# Power.net
KiCad netlist of a schematic drawn in Altium Designer
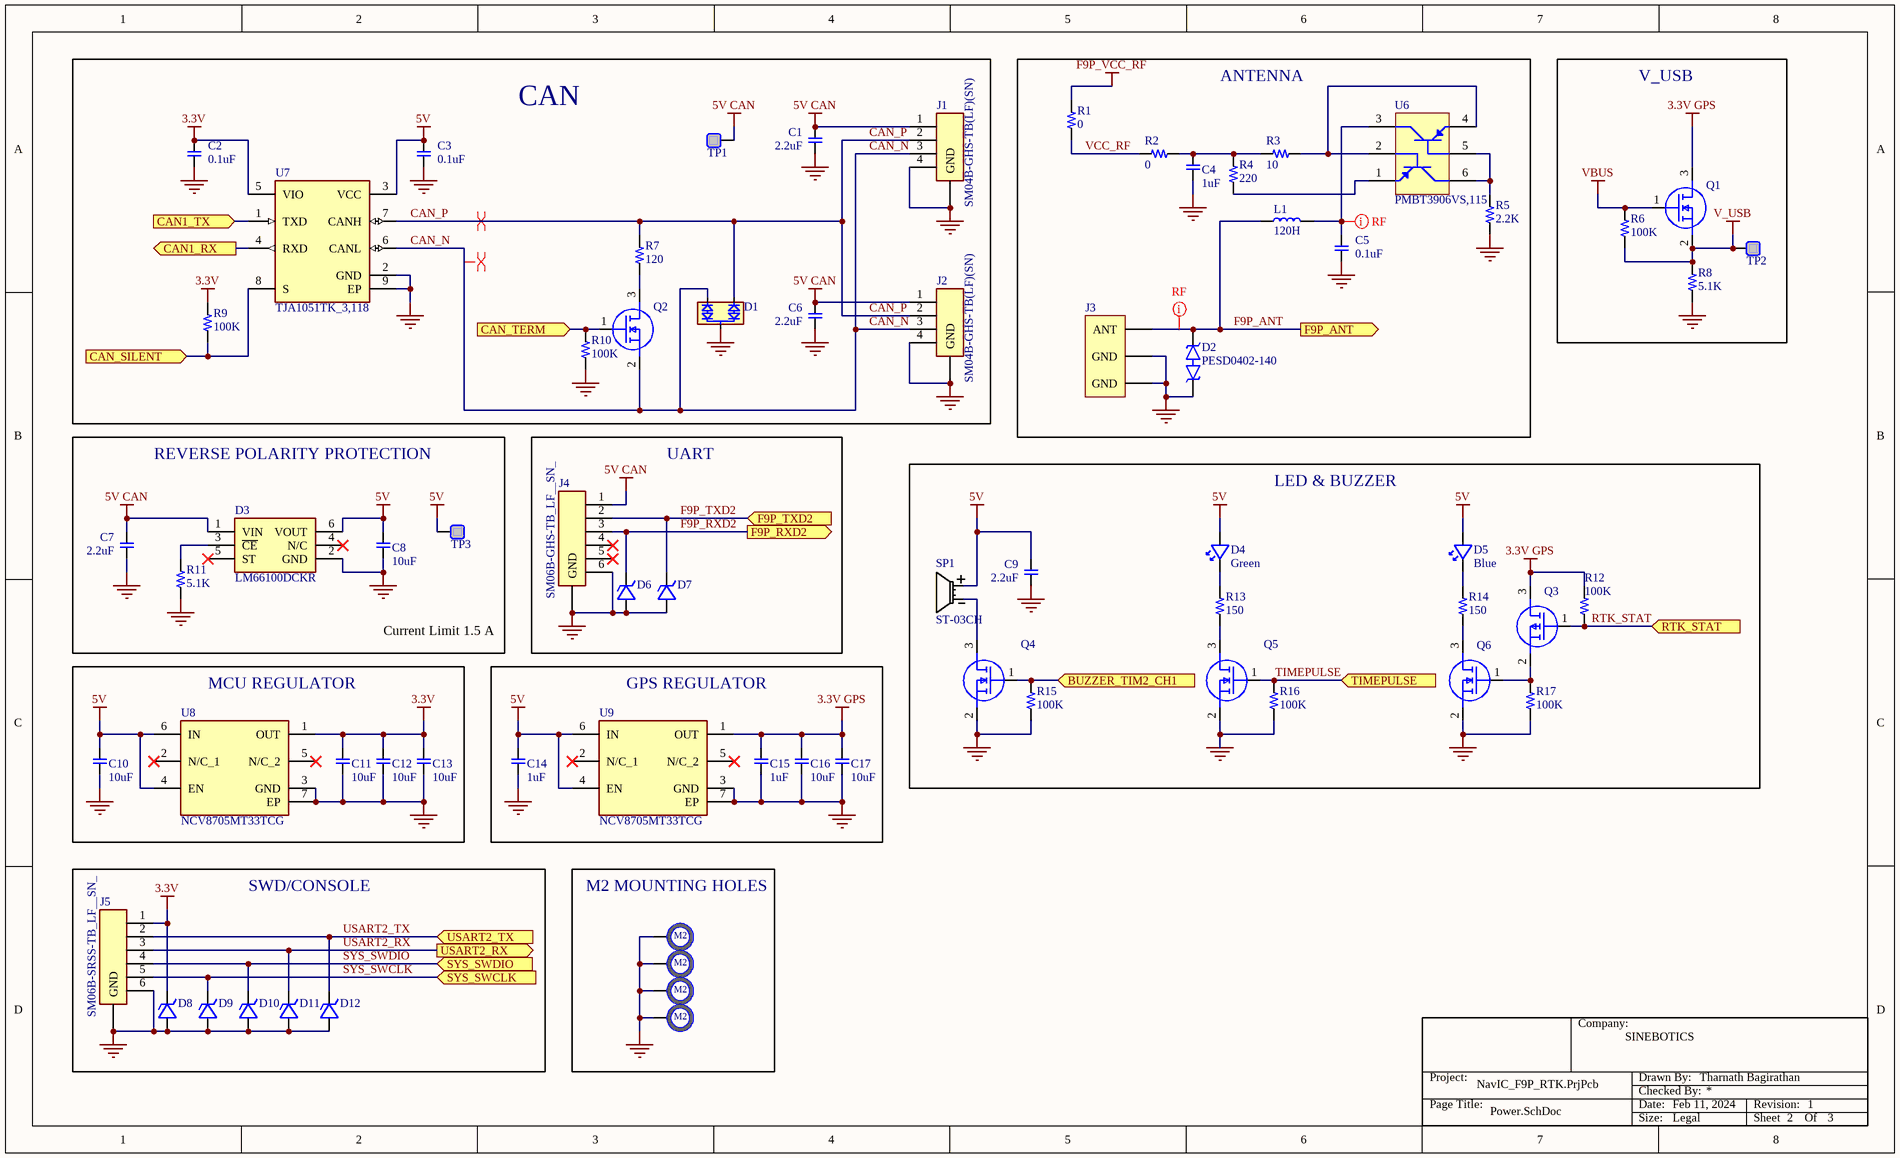
[diagram p0: Power.SchDoc]

(export (version "E")
  (design (tool "Eeschema 10.0.6"))
  (components
    (comp (ref "C1")
      (value "2.2uF")
      (footprint "C0402")
      (description "Capacitor 0402 Generic")
      (fields
        (field (name "MANUFACTURER PART NUMBER") "GRM155R61A225ME95D")
        (field (name "MANUFACTURER") "Murata")
      )
      (libsource (lib "Library") (part "CAP_0402"))
    )
    (comp (ref "C2")
      (value "0.1uF")
      (footprint "C0402")
      (description "Capacitor 0402 Generic")
      (fields
        (field (name "MANUFACTURER PART NUMBER") "0402X104K250CT")
        (field (name "MANUFACTURER") "Walsin Technology Corporation")
      )
      (libsource (lib "Library") (part "CAP_0402"))
    )
    (comp (ref "C3")
      (value "0.1uF")
      (footprint "C0402")
      (description "Capacitor 0402 Generic")
      (fields
        (field (name "MANUFACTURER PART NUMBER") "0402X104K250CT")
        (field (name "MANUFACTURER") "Walsin Technology Corporation")
      )
      (libsource (lib "Library") (part "CAP_0402"))
    )
    (comp (ref "C4")
      (value "1uF")
      (footprint "C0402")
      (description "Capacitor 0402 Generic")
      (fields
        (field (name "MANUFACTURER PART NUMBER") "CL05A105KP5NNNC")
        (field (name "MANUFACTURER") "Samsung Electro-Mechanics")
      )
      (libsource (lib "Library") (part "CAP_0402"))
    )
    (comp (ref "C5")
      (value "0.1uF")
      (footprint "C0402")
      (description "Capacitor 0402 Generic")
      (fields
        (field (name "MANUFACTURER PART NUMBER") "0402X104K250CT")
        (field (name "MANUFACTURER") "Walsin Technology Corporation")
      )
      (libsource (lib "Library") (part "CAP_0402"))
    )
    (comp (ref "C6")
      (value "2.2uF")
      (footprint "C0402")
      (description "Capacitor 0402 Generic")
      (fields
        (field (name "MANUFACTURER PART NUMBER") "GRM155R61A225ME95D")
        (field (name "MANUFACTURER") "Murata")
      )
      (libsource (lib "Library") (part "CAP_0402"))
    )
    (comp (ref "C7")
      (value "2.2uF")
      (footprint "C0402")
      (description "Capacitor 0402 Generic")
      (fields
        (field (name "MANUFACTURER PART NUMBER") "GRM155R61A225ME95D")
        (field (name "MANUFACTURER") "Murata")
      )
      (libsource (lib "Library") (part "CAP_0402"))
    )
    (comp (ref "C8")
      (value "10uF")
      (footprint "C0402")
      (description "Capacitor 0402 Generic")
      (fields
        (field (name "MANUFACTURER PART NUMBER") "CL05A106MP8NUB8")
        (field (name "MANUFACTURER") "Samsung Electro-Mechanics")
      )
      (libsource (lib "Library") (part "CAP_0402"))
    )
    (comp (ref "C9")
      (value "2.2uF")
      (footprint "C0402")
      (description "Capacitor 0402 Generic")
      (fields
        (field (name "MANUFACTURER PART NUMBER") "GRM155R61A225ME95D")
        (field (name "MANUFACTURER") "Murata")
      )
      (libsource (lib "Library") (part "CAP_0402"))
    )
    (comp (ref "C10")
      (value "10uF")
      (footprint "C0402")
      (description "Capacitor 0402 Generic")
      (fields
        (field (name "MANUFACTURER PART NUMBER") "CL05A106MP8NUB8")
        (field (name "MANUFACTURER") "Samsung Electro-Mechanics")
      )
      (libsource (lib "Library") (part "CAP_0402"))
    )
    (comp (ref "C11")
      (value "10uF")
      (footprint "C0402")
      (description "Capacitor 0402 Generic")
      (fields
        (field (name "MANUFACTURER PART NUMBER") "CL05A106MP8NUB8")
        (field (name "MANUFACTURER") "Samsung Electro-Mechanics")
      )
      (libsource (lib "Library") (part "CAP_0402"))
    )
    (comp (ref "C12")
      (value "10uF")
      (footprint "C0402")
      (description "Capacitor 0402 Generic")
      (fields
        (field (name "MANUFACTURER PART NUMBER") "CL05A106MP8NUB8")
        (field (name "MANUFACTURER") "Samsung Electro-Mechanics")
      )
      (libsource (lib "Library") (part "CAP_0402"))
    )
    (comp (ref "C13")
      (value "10uF")
      (footprint "C0402")
      (description "Capacitor 0402 Generic")
      (fields
        (field (name "MANUFACTURER PART NUMBER") "CL05A106MP8NUB8")
        (field (name "MANUFACTURER") "Samsung Electro-Mechanics")
      )
      (libsource (lib "Library") (part "CAP_0402"))
    )
    (comp (ref "C14")
      (value "1uF")
      (footprint "C0402")
      (description "Capacitor 0402 Generic")
      (fields
        (field (name "MANUFACTURER PART NUMBER") "CL05A105KP5NNNC")
        (field (name "MANUFACTURER") "Samsung Electro-Mechanics")
      )
      (libsource (lib "Library") (part "CAP_0402"))
    )
    (comp (ref "C15")
      (value "1uF")
      (footprint "C0402")
      (description "Capacitor 0402 Generic")
      (fields
        (field (name "MANUFACTURER PART NUMBER") "CL05A105KP5NNNC")
        (field (name "MANUFACTURER") "Samsung Electro-Mechanics")
      )
      (libsource (lib "Library") (part "CAP_0402"))
    )
    (comp (ref "C16")
      (value "10uF")
      (footprint "C0402")
      (description "Capacitor 0402 Generic")
      (fields
        (field (name "MANUFACTURER PART NUMBER") "CL05A106MP8NUB8")
        (field (name "MANUFACTURER") "Samsung Electro-Mechanics")
      )
      (libsource (lib "Library") (part "CAP_0402"))
    )
    (comp (ref "C17")
      (value "10uF")
      (footprint "C0402")
      (description "Capacitor 0402 Generic")
      (fields
        (field (name "MANUFACTURER PART NUMBER") "CL05A106MP8NUB8")
        (field (name "MANUFACTURER") "Samsung Electro-Mechanics")
      )
      (libsource (lib "Library") (part "CAP_0402"))
    )
    (comp (ref "D1")
      (value "PESD1CAN-UX")
      (footprint "SamacSys:PESD1CANUX")
      (description "Diode")
      (libsource (lib "SamacSys") (part "PESD1CAN-UX"))
    )
    (comp (ref "D2")
      (value "PESD0402-140")
      (footprint "SamacSys:DIONC1005X43N")
      (description "TVS Diode (Bi-directional)")
      (libsource (lib "SamacSys") (part "PESD0402-140"))
    )
    (comp (ref "D3")
      (value "LM66100DCKR")
      (footprint "SamacSys:SOP65P210X110-6N")
      (description "Diode")
      (libsource (lib "SamacSys") (part "LM66100DCKR"))
    )
    (comp (ref "D4")
      (value "Green")
      (footprint "SamacSys:LTSTS110TBKT")
      (description "LED")
      (fields
        (field (name "ARROW PART NUMBER") "LTST-S110TBKT")
        (field (name "MANUFACTURER PART NUMBER") "LTST-S110KGKT")
      )
      (libsource (lib "Schlib") (part "LTST-S110KGKT"))
    )
    (comp (ref "D5")
      (value "Blue")
      (footprint "SamacSys:LTSTS110TBKT")
      (description "LED")
      (fields (field (name "ARROW PART NUMBER") "LTST-S110TBKT"))
      (libsource (lib "SamacSys") (part "LTST-S110TBKT"))
    )
    (comp (ref "D6")
      (value "ESD9C3.3ST5G")
      (footprint "SamacSys:SODFL1006X40N")
      (description "TVS Diode (Uni-directional)")
      (fields (field (name "ARROW PART NUMBER") "SZESD9C3.3ST5G"))
      (libsource (lib "SamacSys") (part "ESD9C3.3ST5G"))
    )
    (comp (ref "D7")
      (value "ESD9C3.3ST5G")
      (footprint "SamacSys:SODFL1006X40N")
      (description "TVS Diode (Uni-directional)")
      (fields (field (name "ARROW PART NUMBER") "SZESD9C3.3ST5G"))
      (libsource (lib "SamacSys") (part "ESD9C3.3ST5G"))
    )
    (comp (ref "D8")
      (value "ESD9C3.3ST5G")
      (footprint "SamacSys:SODFL1006X40N")
      (description "TVS Diode (Uni-directional)")
      (fields (field (name "ARROW PART NUMBER") "SZESD9C3.3ST5G"))
      (libsource (lib "SamacSys") (part "ESD9C3.3ST5G"))
    )
    (comp (ref "D9")
      (value "ESD9C3.3ST5G")
      (footprint "SamacSys:SODFL1006X40N")
      (description "TVS Diode (Uni-directional)")
      (fields (field (name "ARROW PART NUMBER") "SZESD9C3.3ST5G"))
      (libsource (lib "SamacSys") (part "ESD9C3.3ST5G"))
    )
    (comp (ref "D10")
      (value "ESD9C3.3ST5G")
      (footprint "SamacSys:SODFL1006X40N")
      (description "TVS Diode (Uni-directional)")
      (fields (field (name "ARROW PART NUMBER") "SZESD9C3.3ST5G"))
      (libsource (lib "SamacSys") (part "ESD9C3.3ST5G"))
    )
    (comp (ref "D11")
      (value "ESD9C3.3ST5G")
      (footprint "SamacSys:SODFL1006X40N")
      (description "TVS Diode (Uni-directional)")
      (fields (field (name "ARROW PART NUMBER") "SZESD9C3.3ST5G"))
      (libsource (lib "SamacSys") (part "ESD9C3.3ST5G"))
    )
    (comp (ref "D12")
      (value "ESD9C3.3ST5G")
      (footprint "SamacSys:SODFL1006X40N")
      (description "TVS Diode (Uni-directional)")
      (fields (field (name "ARROW PART NUMBER") "SZESD9C3.3ST5G"))
      (libsource (lib "SamacSys") (part "ESD9C3.3ST5G"))
    )
    (comp (ref "H1") (value "M2") (footprint "Hole_M2") (libsource (lib "Schlib") (part "Hole_M2")))
    (comp (ref "H2") (value "M2") (footprint "Hole_M2") (libsource (lib "Schlib") (part "Hole_M2")))
    (comp (ref "H3") (value "M2") (footprint "Hole_M2") (libsource (lib "Schlib") (part "Hole_M2")))
    (comp (ref "H4") (value "M2") (footprint "Hole_M2") (libsource (lib "Schlib") (part "Hole_M2")))
    (comp (ref "J1")
      (value "SM04B-GHS-TB(LF)(SN)")
      (footprint "SamacSys:SM04B-GHS-TB")
      (description "Connector")
      (libsource (lib "SamacSys") (part "SM04B-GHS-TB(LF)(SN)"))
    )
    (comp (ref "J2")
      (value "SM04B-GHS-TB(LF)(SN)")
      (footprint "SamacSys:SM04B-GHS-TB")
      (description "Connector")
      (libsource (lib "SamacSys") (part "SM04B-GHS-TB(LF)(SN)"))
    )
    (comp (ref "J3")
      (value "0734150963")
      (footprint "PcbLib:MOLEX_0734150963")
      (description "MMCX Connector Jack, Female Socket 50Ohm Board Edge, Cutout; Surface Mount Solder")
      (fields (field (name "MF") "Molex"))
      (libsource (lib "Schlib") (part "0734150963"))
    )
    (comp (ref "J4")
      (value "SM06B-GHS-TB_LF__SN_")
      (footprint "SamacSys:SM06B-GHS-TB")
      (description "Connector")
      (fields (field (name "MANUFACTURER_PART_NUMBER") "SM06B-GHS-TB(LF)(SN)"))
      (libsource (lib "SamacSys") (part "SM06B-GHS-TB_LF__SN_"))
    )
    (comp (ref "J5")
      (value "SM06B-SRSS-TB_LF__SN_")
      (footprint "SamacSys:SM06BSRSSTBLFSN")
      (description "Connector")
      (fields (field (name "MOUSER PART NUMBER") "SM06B-SRSS-TB(LF)(SN)"))
      (libsource (lib "SamacSys") (part "SM06B-SRSS-TB_LF__SN_"))
    )
    (comp (ref "L1")
      (value "120H")
      (footprint "SamacSys:LQW15CNR20J00B")
      (description "Inductor")
      (fields (field (name "ARROW PART NUMBER") "LQW15ANR12J00D"))
      (libsource (lib "SamacSys") (part "LQW15ANR12J00D"))
    )
    (comp (ref "Q1")
      (value "DMN53D0L-7")
      (footprint "SamacSys:SOT96P240X110-3N")
      (description "MOSFET (N-Channel)")
      (libsource (lib "SamacSys") (part "DMN53D0L-7"))
    )
    (comp (ref "Q2")
      (value "DMN53D0L-7")
      (footprint "SamacSys:SOT96P240X110-3N")
      (description "MOSFET (N-Channel)")
      (libsource (lib "SamacSys") (part "DMN53D0L-7"))
    )
    (comp (ref "Q3")
      (value "BSS223PWH6327XTSA1")
      (footprint "SamacSys:SOT65P210X100-3N")
      (description "MOSFET (P-Channel)")
      (libsource (lib "SamacSys") (part "BSS223PWH6327XTSA1"))
    )
    (comp (ref "Q4")
      (value "DMN53D0L-7")
      (footprint "SamacSys:SOT96P240X110-3N")
      (description "MOSFET (N-Channel)")
      (libsource (lib "SamacSys") (part "DMN53D0L-7"))
    )
    (comp (ref "Q5")
      (value "DMN53D0L-7")
      (footprint "SamacSys:SOT96P240X110-3N")
      (description "MOSFET (N-Channel)")
      (libsource (lib "SamacSys") (part "DMN53D0L-7"))
    )
    (comp (ref "Q6")
      (value "DMN53D0L-7")
      (footprint "SamacSys:SOT96P240X110-3N")
      (description "MOSFET (N-Channel)")
      (libsource (lib "SamacSys") (part "DMN53D0L-7"))
    )
    (comp (ref "R1")
      (value "0")
      (footprint "R0402")
      (description "Resistor 0402 Generic")
      (fields
        (field (name "MANUFACTURER") "Yageo")
        (field (name "MANUFACTURER PART NUMBER") "AC0402JR-070RL")
      )
      (libsource (lib "Library") (part "RES_0402"))
    )
    (comp (ref "R2")
      (value "0")
      (footprint "R0402")
      (description "Resistor 0402 Generic")
      (fields
        (field (name "MANUFACTURER") "Yageo")
        (field (name "MANUFACTURER PART NUMBER") "AC0402JR-070RL")
      )
      (libsource (lib "Library") (part "RES_0402"))
    )
    (comp (ref "R3")
      (value "10")
      (footprint "SamacSys:RESC3225X70N")
      (description "Resistor")
      (fields (field (name "MANUFACTURER_PART_NUMBER") "RMCF1210JT10R0"))
      (libsource (lib "SamacSys") (part "RES_10_1/2W"))
    )
    (comp (ref "R4")
      (value "220")
      (footprint "R0402")
      (description "Resistor 0402 Generic")
      (fields
        (field (name "MANUFACTURER") "Stackpole Electronics Inc")
        (field (name "MANUFACTURER PART NUMBER") "RMCF0402JT220R")
      )
      (libsource (lib "Library") (part "RES_0402"))
    )
    (comp (ref "R5")
      (value "2.2K")
      (footprint "R0402")
      (description "Resistor 0402 Generic")
      (fields
        (field (name "MANUFACTURER") "Yageo")
        (field (name "MANUFACTURER PART NUMBER") "AC0402FR-072K2L")
      )
      (libsource (lib "Library") (part "RES_0402"))
    )
    (comp (ref "R6")
      (value "100K")
      (footprint "R0402")
      (description "Resistor 0402 Generic")
      (fields
        (field (name "MANUFACTURER") "Yageo")
        (field (name "MANUFACTURER PART NUMBER") "AC0402JR-07100KL")
      )
      (libsource (lib "Library") (part "RES_0402"))
    )
    (comp (ref "R7")
      (value "120")
      (footprint "SamacSys:RESC1608X55N")
      (description "Resistor")
      (fields (field (name "MANUFACTURER_PART_NUMBER") "RMCF0603FT120R"))
      (libsource (lib "SamacSys") (part "RES_120"))
    )
    (comp (ref "R8")
      (value "5.1K")
      (footprint "R0402")
      (description "Resistor 0402 Generic")
      (fields
        (field (name "MANUFACTURER") "Yageo")
        (field (name "MANUFACTURER PART NUMBER") "RC0402FR-075K1L")
      )
      (libsource (lib "Library") (part "RES_0402"))
    )
    (comp (ref "R9")
      (value "100K")
      (footprint "R0402")
      (description "Resistor 0402 Generic")
      (fields
        (field (name "MANUFACTURER") "Yageo")
        (field (name "MANUFACTURER PART NUMBER") "AC0402JR-07100KL")
      )
      (libsource (lib "Library") (part "RES_0402"))
    )
    (comp (ref "R10")
      (value "100K")
      (footprint "R0402")
      (description "Resistor 0402 Generic")
      (fields
        (field (name "MANUFACTURER") "Yageo")
        (field (name "MANUFACTURER PART NUMBER") "AC0402JR-07100KL")
      )
      (libsource (lib "Library") (part "RES_0402"))
    )
    (comp (ref "R11")
      (value "5.1K")
      (footprint "R0402")
      (description "Resistor 0402 Generic")
      (fields
        (field (name "MANUFACTURER") "Yageo")
        (field (name "MANUFACTURER PART NUMBER") "RC0402FR-075K1L")
      )
      (libsource (lib "Library") (part "RES_0402"))
    )
    (comp (ref "R12")
      (value "100K")
      (footprint "R0402")
      (description "Resistor 0402 Generic")
      (fields
        (field (name "MANUFACTURER") "Yageo")
        (field (name "MANUFACTURER PART NUMBER") "AC0402JR-07100KL")
      )
      (libsource (lib "Library") (part "RES_0402"))
    )
    (comp (ref "R13")
      (value "150")
      (footprint "R0402")
      (description "Resistor 0402 Generic")
      (fields
        (field (name "MANUFACTURER") "Stackpole Electronics Inc")
        (field (name "MANUFACTURER PART NUMBER") "RC0402FR-07150RL")
      )
      (libsource (lib "Library") (part "RES_0402"))
    )
    (comp (ref "R14")
      (value "150")
      (footprint "R0402")
      (description "Resistor 0402 Generic")
      (fields
        (field (name "MANUFACTURER") "Stackpole Electronics Inc")
        (field (name "MANUFACTURER PART NUMBER") "RC0402FR-07150RL")
      )
      (libsource (lib "Library") (part "RES_0402"))
    )
    (comp (ref "R15")
      (value "100K")
      (footprint "R0402")
      (description "Resistor 0402 Generic")
      (fields
        (field (name "MANUFACTURER") "Yageo")
        (field (name "MANUFACTURER PART NUMBER") "AC0402JR-07100KL")
      )
      (libsource (lib "Library") (part "RES_0402"))
    )
    (comp (ref "R16")
      (value "100K")
      (footprint "R0402")
      (description "Resistor 0402 Generic")
      (fields
        (field (name "MANUFACTURER") "Yageo")
        (field (name "MANUFACTURER PART NUMBER") "AC0402JR-07100KL")
      )
      (libsource (lib "Library") (part "RES_0402"))
    )
    (comp (ref "R17")
      (value "100K")
      (footprint "R0402")
      (description "Resistor 0402 Generic")
      (fields
        (field (name "MANUFACTURER") "Yageo")
        (field (name "MANUFACTURER PART NUMBER") "AC0402JR-07100KL")
      )
      (libsource (lib "Library") (part "RES_0402"))
    )
    (comp (ref "SP1")
      (value "ST-03CH")
      (footprint "SamacSys:ST03CH")
      (description "Loudspeaker or Buzzer")
      (libsource (lib "SamacSys") (part "ST-03CH"))
    )
    (comp (ref "TP1")
      (value "TestPad")
      (footprint "TestPad")
      (description "Test Pads")
      (libsource (lib "Schlib") (part "TestPad"))
    )
    (comp (ref "TP2")
      (value "TestPad")
      (footprint "TestPad")
      (description "Test Pads")
      (libsource (lib "Schlib") (part "TestPad"))
    )
    (comp (ref "TP3")
      (value "TestPad")
      (footprint "TestPad")
      (description "Test Pads")
      (libsource (lib "Schlib") (part "TestPad"))
    )
    (comp (ref "U6")
      (value "PMBT3906VS,115")
      (footprint "SamacSys:PMBT3906VS115")
      (description "Transistor BJT PNP")
      (libsource (lib "SamacSys") (part "PMBT3906VS,115"))
    )
    (comp (ref "U7")
      (value "TJA1051TK_3,118")
      (footprint "SamacSys:SON65P300X300X100-9N-D")
      (description "Integrated Circuit")
      (fields (field (name "MANUFACTURER_PART_NUMBER") "TJA1051TK/3,118"))
      (libsource (lib "SamacSys") (part "TJA1051TK_3,118"))
    )
    (comp (ref "U8")
      (value "NCV8705MT33TCG")
      (footprint "SamacSys:SON65P200X200X80-7N")
      (description "Integrated Circuit")
      (libsource (lib "SamacSys") (part "NCV8705MT33TCG"))
    )
    (comp (ref "U9")
      (value "NCV8705MT33TCG")
      (footprint "SamacSys:SON65P200X200X80-7N")
      (description "Integrated Circuit")
      (libsource (lib "SamacSys") (part "NCV8705MT33TCG"))
    )
  )
  (nets
    (net (code "1") (name "/BUZZER_TIM2_CH1") (class "Default")
      (node (ref "Q4") (pin "1") (pinfunction "G_1") (pintype "passive"))
      (node (ref "R15") (pin "2") (pintype "passive"))
    )
    (net (code "2") (name "/CAN1_RX") (class "Default")
      (node (ref "U7") (pin "4") (pinfunction "RXD_4") (pintype "output"))
    )
    (net (code "3") (name "/CAN1_TX") (class "Default")
      (node (ref "U7") (pin "1") (pinfunction "TXD_1") (pintype "input"))
    )
    (net (code "4") (name "/CAN_N") (class "Default")
      (node (ref "D1") (pin "1") (pinfunction "CATHODE_1_1") (pintype "passive"))
      (node (ref "J1") (pin "3") (pinfunction "3_3") (pintype "passive"))
      (node (ref "J2") (pin "3") (pinfunction "3_3") (pintype "passive"))
      (node (ref "Q2") (pin "2") (pinfunction "S_2") (pintype "passive"))
      (node (ref "U7") (pin "6") (pinfunction "CANL_6") (pintype "bidirectional"))
    )
    (net (code "5") (name "/CAN_P") (class "Default")
      (node (ref "D1") (pin "2") (pinfunction "CATHODE_2_2") (pintype "passive"))
      (node (ref "J1") (pin "2") (pinfunction "2_2") (pintype "passive"))
      (node (ref "J2") (pin "2") (pinfunction "2_2") (pintype "passive"))
      (node (ref "R7") (pin "2") (pinfunction "2_2") (pintype "passive"))
      (node (ref "U7") (pin "7") (pinfunction "CANH_7") (pintype "bidirectional"))
    )
    (net (code "6") (name "/CAN_SILENT") (class "Default")
      (node (ref "R9") (pin "1") (pintype "passive"))
      (node (ref "U7") (pin "8") (pinfunction "S_8") (pintype "passive"))
    )
    (net (code "7") (name "/CAN_TERM") (class "Default")
      (node (ref "Q2") (pin "1") (pinfunction "G_1") (pintype "passive"))
      (node (ref "R10") (pin "2") (pintype "passive"))
    )
    (net (code "8") (name "/F9P_ANT") (class "Default")
      (node (ref "D2") (pin "2") (pinfunction "2_2") (pintype "passive"))
      (node (ref "J3") (pin "1") (pinfunction "ANT_1") (pintype "passive"))
      (node (ref "L1") (pin "1") (pinfunction "1_1") (pintype "passive"))
    )
    (net (code "9") (name "/F9P_RXD2") (class "Default")
      (node (ref "D6") (pin "1") (pinfunction "K_1") (pintype "passive"))
      (node (ref "J4") (pin "3") (pinfunction "3_3") (pintype "passive"))
    )
    (net (code "10") (name "/F9P_TXD2") (class "Default")
      (node (ref "D7") (pin "1") (pinfunction "K_1") (pintype "passive"))
      (node (ref "J4") (pin "2") (pinfunction "2_2") (pintype "passive"))
    )
    (net (code "11") (name "/RTK_STAT") (class "Default")
      (node (ref "Q3") (pin "1") (pinfunction "G_1") (pintype "passive"))
      (node (ref "R12") (pin "1") (pintype "passive"))
    )
    (net (code "12") (name "/SYS_SWCLK") (class "Default")
      (node (ref "D9") (pin "1") (pinfunction "K_1") (pintype "passive"))
      (node (ref "J5") (pin "5") (pinfunction "5_5") (pintype "passive"))
    )
    (net (code "13") (name "/SYS_SWDIO") (class "Default")
      (node (ref "D10") (pin "1") (pinfunction "K_1") (pintype "passive"))
      (node (ref "J5") (pin "4") (pinfunction "4_4") (pintype "passive"))
    )
    (net (code "14") (name "/TIMEPULSE") (class "Default")
      (node (ref "Q5") (pin "1") (pinfunction "G_1") (pintype "passive"))
      (node (ref "R16") (pin "2") (pintype "passive"))
    )
    (net (code "15") (name "/USART2_RX") (class "Default")
      (node (ref "D11") (pin "1") (pinfunction "K_1") (pintype "passive"))
      (node (ref "J5") (pin "3") (pinfunction "3_3") (pintype "passive"))
    )
    (net (code "16") (name "/USART2_TX") (class "Default")
      (node (ref "D12") (pin "1") (pinfunction "K_1") (pintype "passive"))
      (node (ref "J5") (pin "2") (pinfunction "2_2") (pintype "passive"))
    )
    (net (code "17") (name "/VCC_RF") (class "Default")
      (node (ref "R1") (pin "1") (pintype "passive"))
      (node (ref "R2") (pin "1") (pintype "passive"))
    )
    (net (code "18") (name "3.3V") (class "Default")
      (node (ref "C11") (pin "1") (pintype "passive"))
      (node (ref "C12") (pin "1") (pintype "passive"))
      (node (ref "C13") (pin "1") (pintype "passive"))
      (node (ref "C2") (pin "2") (pintype "passive"))
      (node (ref "D8") (pin "1") (pinfunction "K_1") (pintype "passive"))
      (node (ref "J5") (pin "1") (pinfunction "1_1") (pintype "passive"))
      (node (ref "R9") (pin "2") (pintype "passive"))
      (node (ref "U7") (pin "5") (pinfunction "VIO_5") (pintype "passive"))
      (node (ref "U8") (pin "1") (pinfunction "OUT_1") (pintype "passive"))
    )
    (net (code "19") (name "3.3V GPS") (class "Default")
      (node (ref "C15") (pin "2") (pintype "passive"))
      (node (ref "C16") (pin "1") (pintype "passive"))
      (node (ref "C17") (pin "1") (pintype "passive"))
      (node (ref "Q1") (pin "3") (pinfunction "D_3") (pintype "passive"))
      (node (ref "Q3") (pin "3") (pinfunction "D_3") (pintype "passive"))
      (node (ref "R12") (pin "2") (pintype "passive"))
      (node (ref "U9") (pin "1") (pinfunction "OUT_1") (pintype "passive"))
    )
    (net (code "20") (name "5V") (class "Default")
      (node (ref "C10") (pin "2") (pintype "passive"))
      (node (ref "C14") (pin "2") (pintype "passive"))
      (node (ref "C3") (pin "2") (pintype "passive"))
      (node (ref "C8") (pin "1") (pintype "passive"))
      (node (ref "C9") (pin "2") (pintype "passive"))
      (node (ref "D3") (pin "6") (pinfunction "VOUT_6") (pintype "passive"))
      (node (ref "D4") (pin "2") (pinfunction "A_2") (pintype "passive"))
      (node (ref "D5") (pin "2") (pinfunction "A_2") (pintype "passive"))
      (node (ref "SP1") (pin "2") (pinfunction "+POLARITY_2") (pintype "passive"))
      (node (ref "TP3") (pin "1") (pinfunction "1_1") (pintype "passive"))
      (node (ref "U7") (pin "3") (pinfunction "VCC_3") (pintype "passive"))
      (node (ref "U8") (pin "4") (pinfunction "EN_4") (pintype "passive"))
      (node (ref "U8") (pin "6") (pinfunction "IN_6") (pintype "passive"))
      (node (ref "U9") (pin "4") (pinfunction "EN_4") (pintype "passive"))
      (node (ref "U9") (pin "6") (pinfunction "IN_6") (pintype "passive"))
    )
    (net (code "21") (name "5V CAN") (class "Default")
      (node (ref "C1") (pin "2") (pintype "passive"))
      (node (ref "C6") (pin "2") (pintype "passive"))
      (node (ref "C7") (pin "2") (pintype "passive"))
      (node (ref "D3") (pin "1") (pinfunction "VIN_1") (pintype "passive"))
      (node (ref "J1") (pin "1") (pinfunction "1_1") (pintype "passive"))
      (node (ref "J2") (pin "1") (pinfunction "1_1") (pintype "passive"))
      (node (ref "J4") (pin "1") (pinfunction "1_1") (pintype "passive"))
      (node (ref "TP1") (pin "1") (pinfunction "1_1") (pintype "passive"))
    )
    (net (code "22") (name "F9P_VCC_RF") (class "Default") (node (ref "R1") (pin "2") (pintype "passive")))
    (net (code "23") (name "GND") (class "Default")
      (node (ref "C1") (pin "1") (pintype "passive"))
      (node (ref "C10") (pin "1") (pintype "passive"))
      (node (ref "C11") (pin "2") (pintype "passive"))
      (node (ref "C12") (pin "2") (pintype "passive"))
      (node (ref "C13") (pin "2") (pintype "passive"))
      (node (ref "C14") (pin "1") (pintype "passive"))
      (node (ref "C15") (pin "1") (pintype "passive"))
      (node (ref "C16") (pin "2") (pintype "passive"))
      (node (ref "C17") (pin "2") (pintype "passive"))
      (node (ref "C2") (pin "1") (pintype "passive"))
      (node (ref "C3") (pin "1") (pintype "passive"))
      (node (ref "C4") (pin "1") (pintype "passive"))
      (node (ref "C5") (pin "1") (pintype "passive"))
      (node (ref "C6") (pin "1") (pintype "passive"))
      (node (ref "C7") (pin "1") (pintype "passive"))
      (node (ref "C8") (pin "2") (pintype "passive"))
      (node (ref "C9") (pin "1") (pintype "passive"))
      (node (ref "D1") (pin "3") (pinfunction "_COMMON_CATHODE_3") (pintype "passive"))
      (node (ref "D10") (pin "2") (pinfunction "A_2") (pintype "passive"))
      (node (ref "D11") (pin "2") (pinfunction "A_2") (pintype "passive"))
      (node (ref "D12") (pin "2") (pinfunction "A_2") (pintype "passive"))
      (node (ref "D2") (pin "1") (pintype "passive"))
      (node (ref "D3") (pin "2") (pinfunction "GND_2") (pintype "passive"))
      (node (ref "D6") (pin "2") (pinfunction "A_2") (pintype "passive"))
      (node (ref "D7") (pin "2") (pinfunction "A_2") (pintype "passive"))
      (node (ref "D8") (pin "2") (pinfunction "A_2") (pintype "passive"))
      (node (ref "D9") (pin "2") (pinfunction "A_2") (pintype "passive"))
      (node (ref "H1") (pin "1") (pinfunction "1_1") (pintype "power_in"))
      (node (ref "H2") (pin "1") (pinfunction "1_1") (pintype "power_in"))
      (node (ref "H3") (pin "1") (pinfunction "1_1") (pintype "power_in"))
      (node (ref "H4") (pin "1") (pinfunction "1_1") (pintype "power_in"))
      (node (ref "J1") (pin "0") (pinfunction "GND_0") (pintype "passive"))
      (node (ref "J1") (pin "4") (pinfunction "4_4") (pintype "passive"))
      (node (ref "J2") (pin "0") (pinfunction "GND_0") (pintype "passive"))
      (node (ref "J2") (pin "4") (pinfunction "4_4") (pintype "passive"))
      (node (ref "J3") (pin "G1") (pinfunction "GND_G1") (pintype "passive"))
      (node (ref "J3") (pin "G2") (pinfunction "GND_G2") (pintype "passive"))
      (node (ref "J4") (pin "6") (pinfunction "6_6") (pintype "passive"))
      (node (ref "J4") (pin "7") (pinfunction "GND_7") (pintype "passive"))
      (node (ref "J5") (pin "6") (pinfunction "6_6") (pintype "passive"))
      (node (ref "J5") (pin "MP") (pinfunction "GND_MP") (pintype "passive"))
      (node (ref "Q4") (pin "2") (pinfunction "S_2") (pintype "passive"))
      (node (ref "Q5") (pin "2") (pinfunction "S_2") (pintype "passive"))
      (node (ref "Q6") (pin "2") (pinfunction "S_2") (pintype "passive"))
      (node (ref "R10") (pin "1") (pintype "passive"))
      (node (ref "R11") (pin "1") (pintype "passive"))
      (node (ref "R15") (pin "1") (pintype "passive"))
      (node (ref "R16") (pin "1") (pintype "passive"))
      (node (ref "R17") (pin "1") (pintype "passive"))
      (node (ref "R5") (pin "1") (pintype "passive"))
      (node (ref "R8") (pin "1") (pintype "passive"))
      (node (ref "U7") (pin "2") (pinfunction "GND_2") (pintype "passive"))
      (node (ref "U7") (pin "9") (pinfunction "EP_9") (pintype "passive"))
      (node (ref "U8") (pin "3") (pinfunction "GND_3") (pintype "passive"))
      (node (ref "U8") (pin "7") (pinfunction "EP_7") (pintype "passive"))
      (node (ref "U9") (pin "3") (pinfunction "GND_3") (pintype "passive"))
      (node (ref "U9") (pin "7") (pinfunction "EP_7") (pintype "passive"))
    )
    (net (code "24") (name "Net-(C4-Pad2)") (class "Default")
      (node (ref "C4") (pin "2") (pintype "passive"))
      (node (ref "R2") (pin "2") (pintype "passive"))
      (node (ref "R3") (pin "1") (pinfunction "1_1") (pintype "passive"))
      (node (ref "R4") (pin "2") (pintype "passive"))
    )
    (net (code "25") (name "Net-(D3-~{CE})") (class "Default")
      (node (ref "D3") (pin "3") (pinfunction "~{CE}_3") (pintype "passive"))
      (node (ref "R11") (pin "2") (pintype "passive"))
    )
    (net (code "26") (name "Net-(D4-K)") (class "Default")
      (node (ref "D4") (pin "1") (pinfunction "K_1") (pintype "passive"))
      (node (ref "R13") (pin "1") (pintype "passive"))
    )
    (net (code "27") (name "Net-(D5-K)") (class "Default")
      (node (ref "D5") (pin "1") (pinfunction "K_1") (pintype "passive"))
      (node (ref "R14") (pin "1") (pintype "passive"))
    )
    (net (code "28") (name "Net-(Q2-D)") (class "Default")
      (node (ref "Q2") (pin "3") (pinfunction "D_3") (pintype "passive"))
      (node (ref "R7") (pin "1") (pinfunction "1_1") (pintype "passive"))
    )
    (net (code "29") (name "Net-(Q3-S)") (class "Default")
      (node (ref "Q3") (pin "2") (pinfunction "S_2") (pintype "passive"))
      (node (ref "Q6") (pin "1") (pinfunction "G_1") (pintype "passive"))
      (node (ref "R17") (pin "2") (pintype "passive"))
    )
    (net (code "30") (name "Net-(Q4-D)") (class "Default")
      (node (ref "Q4") (pin "3") (pinfunction "D_3") (pintype "passive"))
      (node (ref "SP1") (pin "3") (pinfunction "-POLARITY_3") (pintype "passive"))
    )
    (net (code "31") (name "Net-(Q5-D)") (class "Default")
      (node (ref "Q5") (pin "3") (pinfunction "D_3") (pintype "passive"))
      (node (ref "R13") (pin "2") (pintype "passive"))
    )
    (net (code "32") (name "Net-(Q6-D)") (class "Default")
      (node (ref "Q6") (pin "3") (pinfunction "D_3") (pintype "passive"))
      (node (ref "R14") (pin "2") (pintype "passive"))
    )
    (net (code "33") (name "Net-(U6-BASE_TR1)") (class "Default")
      (node (ref "R3") (pin "2") (pinfunction "2_2") (pintype "passive"))
      (node (ref "U6") (pin "2") (pinfunction "BASE_TR1_2") (pintype "passive"))
      (node (ref "U6") (pin "4") (pinfunction "EMITTER_TR2_4") (pintype "passive"))
    )
    (net (code "34") (name "Net-(U6-BASE_TR2)") (class "Default")
      (node (ref "R5") (pin "2") (pintype "passive"))
      (node (ref "U6") (pin "5") (pinfunction "BASE_TR2_5") (pintype "passive"))
      (node (ref "U6") (pin "6") (pinfunction "COLLECTOR_TR1_6") (pintype "passive"))
    )
    (net (code "35") (name "Net-(U6-COLLECTOR_TR2)") (class "Default")
      (node (ref "C5") (pin "2") (pintype "passive"))
      (node (ref "L1") (pin "2") (pinfunction "2_2") (pintype "passive"))
      (node (ref "U6") (pin "3") (pinfunction "COLLECTOR_TR2_3") (pintype "passive"))
    )
    (net (code "36") (name "Net-(U6-EMITTER_TR1)") (class "Default")
      (node (ref "R4") (pin "1") (pintype "passive"))
      (node (ref "U6") (pin "1") (pinfunction "EMITTER_TR1_1") (pintype "passive"))
    )
    (net (code "37") (name "VBUS") (class "Default")
      (node (ref "Q1") (pin "1") (pinfunction "G_1") (pintype "passive"))
      (node (ref "R6") (pin "2") (pintype "passive"))
    )
    (net (code "38") (name "V_USB") (class "Default")
      (node (ref "Q1") (pin "2") (pinfunction "S_2") (pintype "passive"))
      (node (ref "R6") (pin "1") (pintype "passive"))
      (node (ref "R8") (pin "2") (pintype "passive"))
      (node (ref "TP2") (pin "1") (pinfunction "1_1") (pintype "passive"))
    )
    (net (code "39") (name "unconnected-(D3-N{slash}C-Pad4)") (class "Default")
      (node (ref "D3") (pin "4") (pinfunction "N/C_4") (pintype "passive+no_connect"))
    )
    (net (code "40") (name "unconnected-(D3-ST-Pad5)") (class "Default")
      (node (ref "D3") (pin "5") (pinfunction "ST_5") (pintype "passive+no_connect"))
    )
    (net (code "41") (name "unconnected-(J4-Pad4)") (class "Default")
      (node (ref "J4") (pin "4") (pinfunction "4_4") (pintype "passive+no_connect"))
    )
    (net (code "42") (name "unconnected-(J4-Pad5)") (class "Default")
      (node (ref "J4") (pin "5") (pinfunction "5_5") (pintype "passive+no_connect"))
    )
    (net (code "43") (name "unconnected-(SP1-NC_1-Pad1)") (class "Default")
      (node (ref "SP1") (pin "1") (pinfunction "NC_1_1") (pintype "passive"))
    )
    (net (code "44") (name "unconnected-(SP1-NC_2-Pad4)") (class "Default")
      (node (ref "SP1") (pin "4") (pinfunction "NC_2_4") (pintype "passive"))
    )
    (net (code "45") (name "unconnected-(U8-N{slash}C_1-Pad2)") (class "Default")
      (node (ref "U8") (pin "2") (pinfunction "N/C_1_2") (pintype "passive+no_connect"))
    )
    (net (code "46") (name "unconnected-(U8-N{slash}C_2-Pad5)") (class "Default")
      (node (ref "U8") (pin "5") (pinfunction "N/C_2_5") (pintype "passive+no_connect"))
    )
    (net (code "47") (name "unconnected-(U9-N{slash}C_1-Pad2)") (class "Default")
      (node (ref "U9") (pin "2") (pinfunction "N/C_1_2") (pintype "passive+no_connect"))
    )
    (net (code "48") (name "unconnected-(U9-N{slash}C_2-Pad5)") (class "Default")
      (node (ref "U9") (pin "5") (pinfunction "N/C_2_5") (pintype "passive+no_connect"))
    )
  )
)
